# FPGA_Tester_Board_Signals.net
KiCad netlist of a schematic drawn in Altium Designer
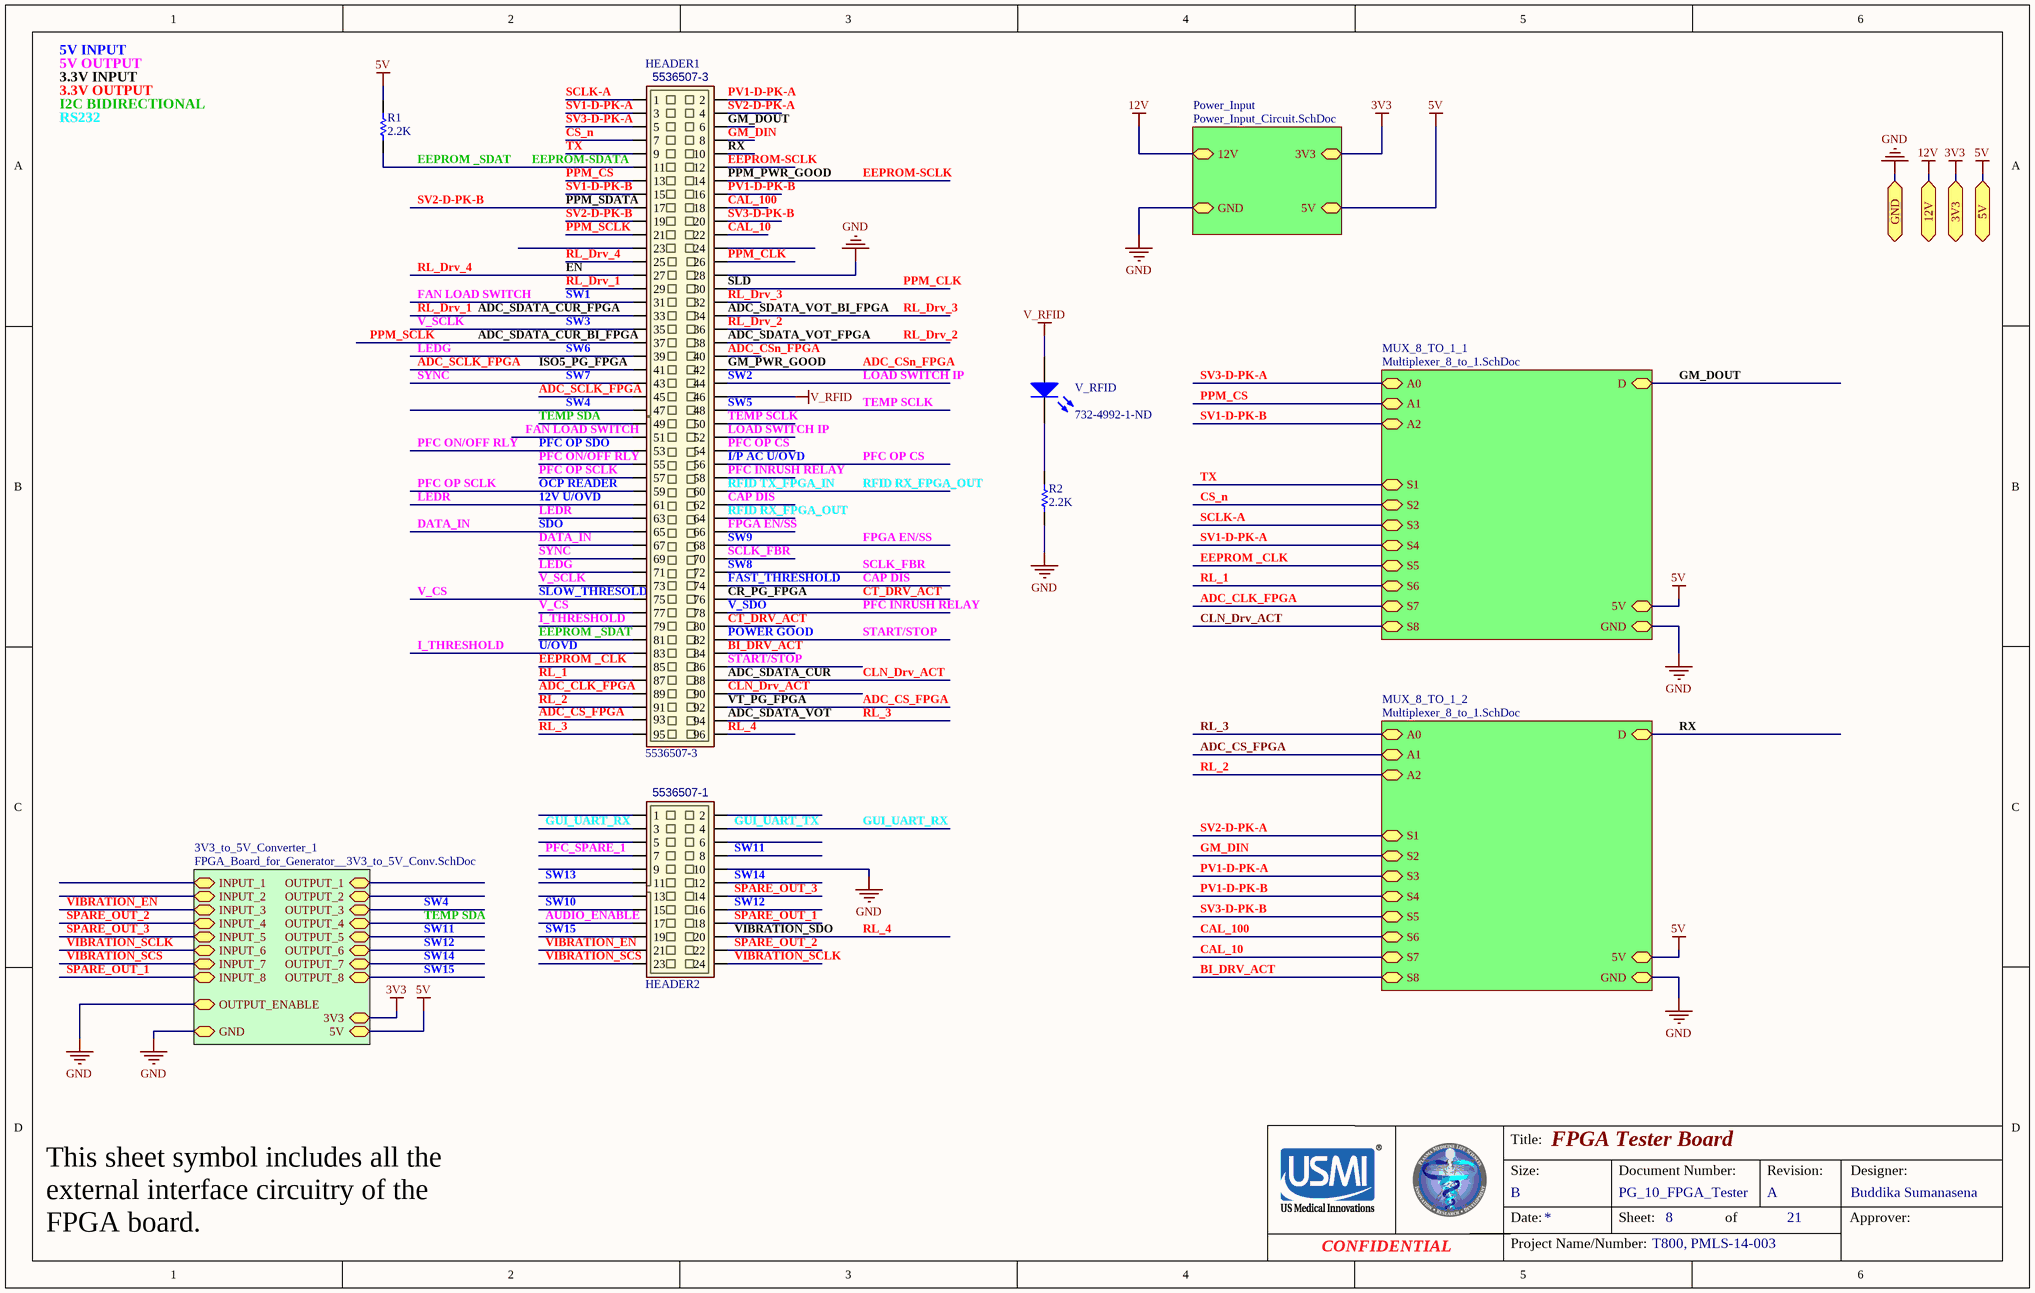
[diagram p0: FPGA_Tester_Board_Signals.SchDoc]

(export (version "E")
  (design (tool "Eeschema 10.0.6"))
  (components
    (comp (ref "HEADER1")
      (value "5536507-3")
      (footprint "5536501-3")
      (description "TE Z-Pack 5536507-3")
      (libsource (lib "ES_LIB") (part "5536507-3"))
    )
    (comp (ref "HEADER2")
      (value "5536507-1")
      (footprint "5536501-1")
      (description "TE Z-Pack 5536507-1")
      (libsource (lib "ES_LIB") (part "5536507-1"))
    )
    (comp (ref "R1")
      (value "2.2K")
      (footprint "0603R")
      (description "Resistor")
      (fields (field (name "PUBLISHER") "Altium Limited"))
      (libsource (lib "Buddika Miscellaneous Devices") (part "Res1"))
    )
    (comp (ref "R2")
      (value "2.2K")
      (footprint "0603R")
      (description "Resistor")
      (fields (field (name "PUBLISHER") "Altium Limited"))
      (libsource (lib "Buddika Miscellaneous Devices") (part "Res1"))
    )
    (comp (ref "V_RFID")
      (value "RED")
      (footprint "1206_A")
      (description "SMD mono-color Chip LED, WL-SMCW, Super Red")
      (fields
        (field (name "MANUFACTURER") "Wuerth Elektronik")
        (field (name "PARTNUMBER") "150120SS75000")
        (field (name "SUPPLIER PART NUMBER 1") "732-4992-1-ND")
      )
      (libsource (lib "Altium Content Vault") (part "CMP-1426-00017-1"))
    )
  )
  (nets
    (net (code "1") (name "/12V U{slash}OVD") (class "Default")
      (node (ref "HEADER1") (pin "61") (pinfunction "61_61") (pintype "passive"))
      (node (ref "HEADER1") (pin "63") (pinfunction "63_63") (pintype "passive"))
    )
    (net (code "2") (name "/ADC_CLK_FPGA") (class "Default")
      (node (ref "HEADER1") (pin "89") (pinfunction "89_89") (pintype "passive"))
    )
    (net (code "3") (name "/ADC_CS_FPGA") (class "Default")
      (node (ref "HEADER1") (pin "92") (pinfunction "92_92") (pintype "passive"))
      (node (ref "HEADER1") (pin "93") (pinfunction "93_93") (pintype "passive"))
    )
    (net (code "4") (name "/ADC_CSn_FPGA") (class "Default")
      (node (ref "HEADER1") (pin "40") (pinfunction "40_40") (pintype "passive"))
      (node (ref "HEADER1") (pin "42") (pinfunction "42_42") (pintype "passive"))
    )
    (net (code "5") (name "/ADC_SCLK_FPGA") (class "Default")
      (node (ref "HEADER1") (pin "41") (pinfunction "41_41") (pintype "passive"))
      (node (ref "HEADER1") (pin "45") (pinfunction "45_45") (pintype "passive"))
    )
    (net (code "6") (name "/ADC_SDATA_CUR") (class "Default")
      (node (ref "HEADER1") (pin "88") (pinfunction "88_88") (pintype "passive"))
      (node (ref "HEADER1") (pin "90") (pinfunction "90_90") (pintype "passive"))
    )
    (net (code "7") (name "/ADC_SDATA_CUR_BI_FPGA") (class "Default")
      (node (ref "HEADER1") (pin "21") (pinfunction "21_21") (pintype "passive"))
      (node (ref "HEADER1") (pin "37") (pinfunction "37_37") (pintype "passive"))
    )
    (net (code "8") (name "/ADC_SDATA_CUR_FPGA") (class "Default")
      (node (ref "HEADER1") (pin "29") (pinfunction "29_29") (pintype "passive"))
      (node (ref "HEADER1") (pin "33") (pinfunction "33_33") (pintype "passive"))
    )
    (net (code "9") (name "/ADC_SDATA_VOT") (class "Default")
      (node (ref "HEADER1") (pin "94") (pinfunction "94_94") (pintype "passive"))
      (node (ref "HEADER1") (pin "95") (pinfunction "95_95") (pintype "passive"))
    )
    (net (code "10") (name "/ADC_SDATA_VOT_BI_FPGA") (class "Default")
      (node (ref "HEADER1") (pin "32") (pinfunction "32_32") (pintype "passive"))
      (node (ref "HEADER1") (pin "34") (pinfunction "34_34") (pintype "passive"))
    )
    (net (code "11") (name "/ADC_SDATA_VOT_FPGA") (class "Default")
      (node (ref "HEADER1") (pin "36") (pinfunction "36_36") (pintype "passive"))
      (node (ref "HEADER1") (pin "38") (pinfunction "38_38") (pintype "passive"))
    )
    (net (code "12") (name "/AUDIO_ENABLE") (class "Default")
      (node (ref "HEADER2") (pin "17") (pinfunction "17_17") (pintype "passive"))
    )
    (net (code "13") (name "/BI_DRV_ACT") (class "Default")
      (node (ref "HEADER1") (pin "84") (pinfunction "84_84") (pintype "passive"))
    )
    (net (code "14") (name "/CAL_10") (class "Default")
      (node (ref "HEADER1") (pin "22") (pinfunction "22_22") (pintype "passive"))
    )
    (net (code "15") (name "/CAL_100") (class "Default")
      (node (ref "HEADER1") (pin "18") (pinfunction "18_18") (pintype "passive"))
    )
    (net (code "16") (name "/CAP DIS") (class "Default")
      (node (ref "HEADER1") (pin "62") (pinfunction "62_62") (pintype "passive"))
      (node (ref "HEADER1") (pin "74") (pinfunction "74_74") (pintype "passive"))
    )
    (net (code "17") (name "/CR_PG_FPGA") (class "Default")
      (node (ref "HEADER1") (pin "76") (pinfunction "76_76") (pintype "passive"))
      (node (ref "HEADER1") (pin "80") (pinfunction "80_80") (pintype "passive"))
    )
    (net (code "18") (name "/CS_n") (class "Default")
      (node (ref "HEADER1") (pin "7") (pinfunction "7_7") (pintype "passive"))
    )
    (net (code "19") (name "/DATA_IN") (class "Default")
      (node (ref "HEADER1") (pin "65") (pinfunction "65_65") (pintype "passive"))
      (node (ref "HEADER1") (pin "67") (pinfunction "67_67") (pintype "passive"))
    )
    (net (code "20") (name "/EEPROM _CLK") (class "Default")
      (node (ref "HEADER1") (pin "85") (pinfunction "85_85") (pintype "passive"))
    )
    (net (code "21") (name "/EEPROM _SDAT") (class "Default")
      (node (ref "HEADER1") (pin "11") (pinfunction "11_11") (pintype "passive"))
      (node (ref "HEADER1") (pin "81") (pinfunction "81_81") (pintype "passive"))
      (node (ref "R1") (pin "1") (pinfunction "1_1") (pintype "passive"))
    )
    (net (code "22") (name "/EEPROM-SCLK") (class "Default")
      (node (ref "HEADER1") (pin "12") (pinfunction "12_12") (pintype "passive"))
      (node (ref "HEADER1") (pin "14") (pinfunction "14_14") (pintype "passive"))
    )
    (net (code "23") (name "/EN") (class "Default")
      (node (ref "HEADER1") (pin "25") (pinfunction "25_25") (pintype "passive"))
      (node (ref "HEADER1") (pin "27") (pinfunction "27_27") (pintype "passive"))
    )
    (net (code "24") (name "/FAN LOAD SWITCH") (class "Default")
      (node (ref "HEADER1") (pin "31") (pinfunction "31_31") (pintype "passive"))
      (node (ref "HEADER1") (pin "51") (pinfunction "51_51") (pintype "passive"))
    )
    (net (code "25") (name "/FPGA EN{slash}SS") (class "Default")
      (node (ref "HEADER1") (pin "66") (pinfunction "66_66") (pintype "passive"))
      (node (ref "HEADER1") (pin "68") (pinfunction "68_68") (pintype "passive"))
    )
    (net (code "26") (name "/GM_DIN") (class "Default")
      (node (ref "HEADER1") (pin "8") (pinfunction "8_8") (pintype "passive"))
    )
    (net (code "27") (name "/GM_DOUT") (class "Default")
      (node (ref "HEADER1") (pin "6") (pinfunction "6_6") (pintype "passive"))
    )
    (net (code "28") (name "/GUI_UART_RX") (class "Default")
      (node (ref "HEADER2") (pin "3") (pinfunction "3_3") (pintype "passive"))
      (node (ref "HEADER2") (pin "4") (pinfunction "4_4") (pintype "passive"))
    )
    (net (code "31") (name "/I_THRESHOLD") (class "Default")
      (node (ref "HEADER1") (pin "79") (pinfunction "79_79") (pintype "passive"))
      (node (ref "HEADER1") (pin "83") (pinfunction "83_83") (pintype "passive"))
    )
    (net (code "32") (name "/I{slash}P AC U{slash}OVD") (class "Default")
      (node (ref "HEADER1") (pin "54") (pinfunction "54_54") (pintype "passive"))
      (node (ref "HEADER1") (pin "56") (pinfunction "56_56") (pintype "passive"))
    )
    (net (code "33") (name "/LEDG") (class "Default")
      (node (ref "HEADER1") (pin "39") (pinfunction "39_39") (pintype "passive"))
      (node (ref "HEADER1") (pin "71") (pinfunction "71_71") (pintype "passive"))
    )
    (net (code "34") (name "/LOAD SWITCH IP") (class "Default")
      (node (ref "HEADER1") (pin "44") (pinfunction "44_44") (pintype "passive"))
      (node (ref "HEADER1") (pin "52") (pinfunction "52_52") (pintype "passive"))
    )
    (net (code "35") (name "/OCP READER") (class "Default")
      (node (ref "HEADER1") (pin "57") (pinfunction "57_57") (pintype "passive"))
      (node (ref "HEADER1") (pin "59") (pinfunction "59_59") (pintype "passive"))
    )
    (net (code "38") (name "/PFC INRUSH RELAY") (class "Default")
      (node (ref "HEADER1") (pin "58") (pinfunction "58_58") (pintype "passive"))
      (node (ref "HEADER1") (pin "78") (pinfunction "78_78") (pintype "passive"))
    )
    (net (code "39") (name "/PFC ON{slash}OFF RLY") (class "Default")
      (node (ref "HEADER1") (pin "53") (pinfunction "53_53") (pintype "passive"))
      (node (ref "HEADER1") (pin "55") (pinfunction "55_55") (pintype "passive"))
    )
    (net (code "40") (name "/PFC_SPARE_1") (class "Default")
      (node (ref "HEADER2") (pin "7") (pinfunction "7_7") (pintype "passive"))
    )
    (net (code "41") (name "/POWER GOOD") (class "Default")
      (node (ref "HEADER1") (pin "82") (pinfunction "82_82") (pintype "passive"))
      (node (ref "HEADER1") (pin "86") (pinfunction "86_86") (pintype "passive"))
    )
    (net (code "42") (name "/PPM_CLK") (class "Default")
      (node (ref "HEADER1") (pin "26") (pinfunction "26_26") (pintype "passive"))
      (node (ref "HEADER1") (pin "30") (pinfunction "30_30") (pintype "passive"))
    )
    (net (code "43") (name "/PPM_CS") (class "Default")
      (node (ref "HEADER1") (pin "13") (pinfunction "13_13") (pintype "passive"))
    )
    (net (code "44") (name "/PPM_SDATA") (class "Default")
      (node (ref "HEADER1") (pin "17") (pinfunction "17_17") (pintype "passive"))
      (node (ref "HEADER1") (pin "19") (pinfunction "19_19") (pintype "passive"))
    )
    (net (code "45") (name "/PV1-D-PK-A") (class "Default")
      (node (ref "HEADER1") (pin "2") (pinfunction "2_2") (pintype "passive"))
    )
    (net (code "46") (name "/PV1-D-PK-B") (class "Default")
      (node (ref "HEADER1") (pin "16") (pinfunction "16_16") (pintype "passive"))
    )
    (net (code "47") (name "/RFID RX_FPGA_OUT") (class "Default")
      (node (ref "HEADER1") (pin "60") (pinfunction "60_60") (pintype "passive"))
      (node (ref "HEADER1") (pin "64") (pinfunction "64_64") (pintype "passive"))
    )
    (net (code "48") (name "/RL_1") (class "Default")
      (node (ref "HEADER1") (pin "87") (pinfunction "87_87") (pintype "passive"))
    )
    (net (code "49") (name "/RL_2") (class "Default")
      (node (ref "HEADER1") (pin "91") (pinfunction "91_91") (pintype "passive"))
    )
    (net (code "50") (name "/RL_4") (class "Default")
      (node (ref "HEADER1") (pin "96") (pinfunction "96_96") (pintype "passive"))
      (node (ref "HEADER2") (pin "20") (pinfunction "20_20") (pintype "passive"))
    )
    (net (code "51") (name "/RX") (class "Default")
      (node (ref "HEADER1") (pin "10") (pinfunction "10_10") (pintype "passive"))
    )
    (net (code "52") (name "/SCLK-A") (class "Default")
      (node (ref "HEADER1") (pin "1") (pinfunction "1_1") (pintype "passive"))
    )
    (net (code "53") (name "/SCLK_FBR") (class "Default")
      (node (ref "HEADER1") (pin "70") (pinfunction "70_70") (pintype "passive"))
      (node (ref "HEADER1") (pin "72") (pinfunction "72_72") (pintype "passive"))
    )
    (net (code "54") (name "/SLOW_THRESOLD") (class "Default")
      (node (ref "HEADER1") (pin "75") (pinfunction "75_75") (pintype "passive"))
      (node (ref "HEADER1") (pin "77") (pinfunction "77_77") (pintype "passive"))
    )
    (net (code "55") (name "/SPARE_OUT_1") (class "Default")
      (node (ref "HEADER2") (pin "18") (pinfunction "18_18") (pintype "passive"))
    )
    (net (code "56") (name "/SPARE_OUT_2") (class "Default")
      (node (ref "HEADER2") (pin "22") (pinfunction "22_22") (pintype "passive"))
    )
    (net (code "57") (name "/SPARE_OUT_3") (class "Default")
      (node (ref "HEADER2") (pin "14") (pinfunction "14_14") (pintype "passive"))
    )
    (net (code "58") (name "/SV1-D-PK-A") (class "Default")
      (node (ref "HEADER1") (pin "3") (pinfunction "3_3") (pintype "passive"))
    )
    (net (code "59") (name "/SV1-D-PK-B") (class "Default")
      (node (ref "HEADER1") (pin "15") (pinfunction "15_15") (pintype "passive"))
    )
    (net (code "60") (name "/SV2-D-PK-A") (class "Default")
      (node (ref "HEADER1") (pin "4") (pinfunction "4_4") (pintype "passive"))
    )
    (net (code "61") (name "/SV3-D-PK-A") (class "Default")
      (node (ref "HEADER1") (pin "5") (pinfunction "5_5") (pintype "passive"))
    )
    (net (code "62") (name "/SV3-D-PK-B") (class "Default")
      (node (ref "HEADER1") (pin "20") (pinfunction "20_20") (pintype "passive"))
    )
    (net (code "63") (name "/SW3") (class "Default")
      (node (ref "HEADER1") (pin "35") (pinfunction "35_35") (pintype "passive"))
      (node (ref "HEADER1") (pin "73") (pinfunction "73_73") (pintype "passive"))
    )
    (net (code "64") (name "/SW4") (class "Default")
      (node (ref "HEADER1") (pin "47") (pinfunction "47_47") (pintype "passive"))
    )
    (net (code "65") (name "/SW5") (class "Default")
      (node (ref "HEADER1") (pin "48") (pinfunction "48_48") (pintype "passive"))
      (node (ref "HEADER1") (pin "50") (pinfunction "50_50") (pintype "passive"))
    )
    (net (code "66") (name "/SW7") (class "Default")
      (node (ref "HEADER1") (pin "43") (pinfunction "43_43") (pintype "passive"))
      (node (ref "HEADER1") (pin "69") (pinfunction "69_69") (pintype "passive"))
    )
    (net (code "67") (name "/SW10") (class "Default")
      (node (ref "HEADER2") (pin "15") (pinfunction "15_15") (pintype "passive"))
    )
    (net (code "68") (name "/SW11") (class "Default")
      (node (ref "HEADER2") (pin "8") (pinfunction "8_8") (pintype "passive"))
    )
    (net (code "69") (name "/SW12") (class "Default")
      (node (ref "HEADER2") (pin "16") (pinfunction "16_16") (pintype "passive"))
    )
    (net (code "70") (name "/SW13") (class "Default")
      (node (ref "HEADER2") (pin "11") (pinfunction "11_11") (pintype "passive"))
    )
    (net (code "71") (name "/SW14") (class "Default")
      (node (ref "HEADER2") (pin "12") (pinfunction "12_12") (pintype "passive"))
    )
    (net (code "72") (name "/SW15") (class "Default")
      (node (ref "HEADER2") (pin "19") (pinfunction "19_19") (pintype "passive"))
    )
    (net (code "73") (name "/TEMP SDA") (class "Default")
      (node (ref "HEADER1") (pin "49") (pinfunction "49_49") (pintype "passive"))
    )
    (net (code "74") (name "/TX") (class "Default")
      (node (ref "HEADER1") (pin "9") (pinfunction "9_9") (pintype "passive"))
    )
    (net (code "75") (name "/VIBRATION_EN") (class "Default")
      (node (ref "HEADER2") (pin "21") (pinfunction "21_21") (pintype "passive"))
    )
    (net (code "76") (name "/VIBRATION_SCLK") (class "Default")
      (node (ref "HEADER2") (pin "24") (pinfunction "24_24") (pintype "passive"))
    )
    (net (code "77") (name "/VIBRATION_SCS") (class "Default")
      (node (ref "HEADER2") (pin "23") (pinfunction "23_23") (pintype "passive"))
    )
    (net (code "79") (name "5V") (class "Default")
      (node (ref "R1") (pin "2") (pinfunction "2_2") (pintype "passive"))
    )
    (net (code "81") (name "GND") (class "Default")
      (node (ref "HEADER1") (pin "28") (pinfunction "28_28") (pintype "passive"))
      (node (ref "HEADER2") (pin "10") (pinfunction "10_10") (pintype "passive"))
      (node (ref "R2") (pin "1") (pinfunction "1_1") (pintype "passive"))
    )
    (net (code "82") (name "Net-(V_RFID-K)") (class "Default")
      (node (ref "R2") (pin "2") (pinfunction "2_2") (pintype "passive"))
      (node (ref "V_RFID") (pin "1") (pinfunction "K_1") (pintype "passive"))
    )
    (net (code "83") (name "V_RFID") (class "Default")
      (node (ref "HEADER1") (pin "46") (pinfunction "46_46") (pintype "passive"))
      (node (ref "V_RFID") (pin "2") (pinfunction "A_2") (pintype "passive"))
    )
    (net (code "84") (name "unconnected-(HEADER1-Pad23)") (class "Default")
      (node (ref "HEADER1") (pin "23") (pinfunction "23_23") (pintype "passive"))
    )
    (net (code "85") (name "unconnected-(HEADER1-Pad24)") (class "Default")
      (node (ref "HEADER1") (pin "24") (pinfunction "24_24") (pintype "passive"))
    )
    (net (code "86") (name "unconnected-(HEADER2-Pad1)") (class "Default")
      (node (ref "HEADER2") (pin "1") (pinfunction "1_1") (pintype "passive"))
    )
    (net (code "87") (name "unconnected-(HEADER2-Pad2)") (class "Default")
      (node (ref "HEADER2") (pin "2") (pinfunction "2_2") (pintype "passive"))
    )
    (net (code "88") (name "unconnected-(HEADER2-Pad5)") (class "Default")
      (node (ref "HEADER2") (pin "5") (pinfunction "5_5") (pintype "passive"))
    )
    (net (code "89") (name "unconnected-(HEADER2-Pad6)") (class "Default")
      (node (ref "HEADER2") (pin "6") (pinfunction "6_6") (pintype "passive"))
    )
    (net (code "90") (name "unconnected-(HEADER2-Pad9)") (class "Default")
      (node (ref "HEADER2") (pin "9") (pinfunction "9_9") (pintype "passive"))
    )
    (net (code "91") (name "unconnected-(HEADER2-Pad13)") (class "Default")
      (node (ref "HEADER2") (pin "13") (pinfunction "13_13") (pintype "passive"))
    )
  )
)
